# CatuDaya.net
KiCad netlist of a schematic drawn in EAGLE
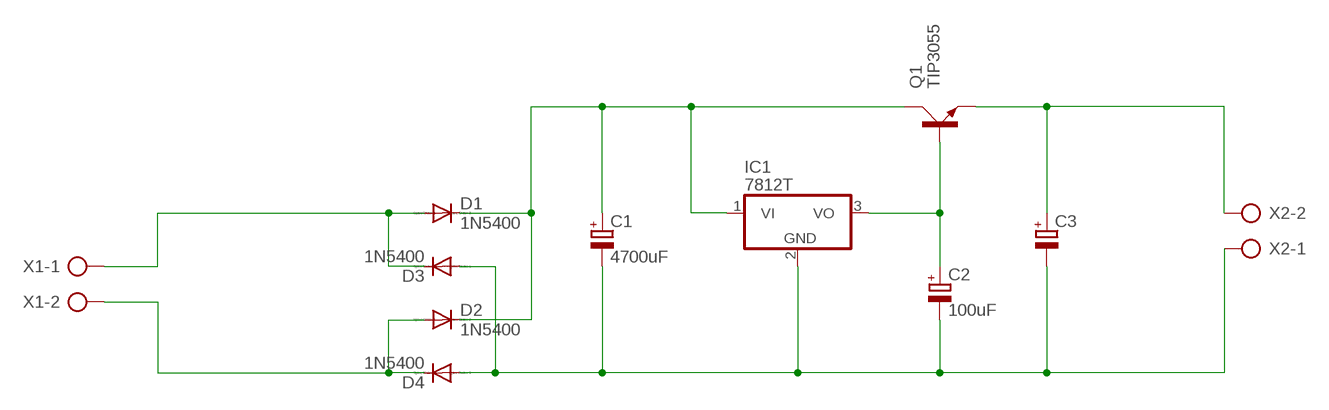
[diagram p0: schematic, sheet 1]

(export (version "E")
  (design (tool "Eeschema 10.0.6"))
  (components
    (comp (ref "C1")
      (value "4700uF")
      (footprint "eagle-import:E7,5-16")
      (libsource (lib "eagle-import") (part "CPOL-EUE7.5-16"))
    )
    (comp (ref "C2")
      (value "100uF")
      (footprint "eagle-import:E2,5-5")
      (libsource (lib "eagle-import") (part "CPOL-EUE2.5-5"))
    )
    (comp (ref "C3")
      (value "CPOL-EUE5-10.5")
      (footprint "eagle-import:E5-10,5")
      (libsource (lib "eagle-import") (part "CPOL-EUE5-10.5"))
    )
    (comp (ref "D1")
      (value "1N5400")
      (footprint "eagle-import:DO201-15")
      (libsource (lib "eagle-import") (part "1N5400"))
    )
    (comp (ref "D2")
      (value "1N5400")
      (footprint "eagle-import:DO201-15")
      (libsource (lib "eagle-import") (part "1N5400"))
    )
    (comp (ref "D3")
      (value "1N5400")
      (footprint "eagle-import:DO201-15")
      (libsource (lib "eagle-import") (part "1N5400"))
    )
    (comp (ref "D4")
      (value "1N5400")
      (footprint "eagle-import:DO201-15")
      (libsource (lib "eagle-import") (part "1N5400"))
    )
    (comp (ref "IC1")
      (value "7812T")
      (footprint "eagle-import:TO220H")
      (libsource (lib "eagle-import") (part "78T12"))
    )
    (comp (ref "Q1")
      (value "TIP3055")
      (footprint "eagle-import:TOP3AV")
      (libsource (lib "eagle-import") (part "TIP3055"))
    )
    (comp (ref "X1")
      (value "AK300/2")
      (footprint "eagle-import:AK300_2")
      (libsource (lib "eagle-import") (part "AK300/2"))
    )
    (comp (ref "X2")
      (value "AK300/2")
      (footprint "eagle-import:AK300_2")
      (libsource (lib "eagle-import") (part "AK300/2"))
    )
  )
  (nets
    (net (code "1") (name "Net-(IC1-GND)") (class "Default")
      (node (ref "C1") (pin "-") (pinfunction "-_-") (pintype "passive"))
      (node (ref "C2") (pin "-") (pinfunction "-_-") (pintype "passive"))
      (node (ref "C3") (pin "-") (pinfunction "-_-") (pintype "passive"))
      (node (ref "D3") (pin "A") (pinfunction "A_A") (pintype "passive"))
      (node (ref "D4") (pin "A") (pinfunction "A_A") (pintype "passive"))
      (node (ref "IC1") (pin "2") (pinfunction "GND_2") (pintype "passive"))
      (node (ref "X2") (pin "1") (pinfunction "KL_1") (pintype "passive"))
    )
    (net (code "2") (name "Net-(IC1-VI)") (class "Default")
      (node (ref "C1") (pin "+") (pinfunction "+_+") (pintype "passive"))
      (node (ref "D1") (pin "C") (pinfunction "C_C") (pintype "passive"))
      (node (ref "D2") (pin "C") (pinfunction "C_C") (pintype "passive"))
      (node (ref "IC1") (pin "1") (pinfunction "VI_1") (pintype "input"))
      (node (ref "Q1") (pin "C") (pinfunction "C_C") (pintype "passive"))
    )
    (net (code "3") (name "Net-(IC1-VO)") (class "Default")
      (node (ref "C2") (pin "+") (pinfunction "+_+") (pintype "passive"))
      (node (ref "IC1") (pin "3") (pinfunction "VO_3") (pintype "passive"))
      (node (ref "Q1") (pin "B") (pinfunction "B_B") (pintype "passive"))
    )
    (net (code "4") (name "Net-(X1A-KL)") (class "Default")
      (node (ref "D1") (pin "A") (pinfunction "A_A") (pintype "passive"))
      (node (ref "D3") (pin "C") (pinfunction "C_C") (pintype "passive"))
      (node (ref "X1") (pin "1") (pinfunction "KL_1") (pintype "passive"))
    )
    (net (code "5") (name "Net-(X1B-KL)") (class "Default")
      (node (ref "D2") (pin "A") (pinfunction "A_A") (pintype "passive"))
      (node (ref "D4") (pin "C") (pinfunction "C_C") (pintype "passive"))
      (node (ref "X1") (pin "2") (pinfunction "KL_2") (pintype "passive"))
    )
    (net (code "6") (name "Net-(X2B-KL)") (class "Default")
      (node (ref "C3") (pin "+") (pinfunction "+_+") (pintype "passive"))
      (node (ref "Q1") (pin "E") (pinfunction "E_E") (pintype "passive"))
      (node (ref "X2") (pin "2") (pinfunction "KL_2") (pintype "passive"))
    )
  )
)
